# V4-AddOnESP32-V001-komplett.net
KiCad netlist of a schematic drawn in EAGLE
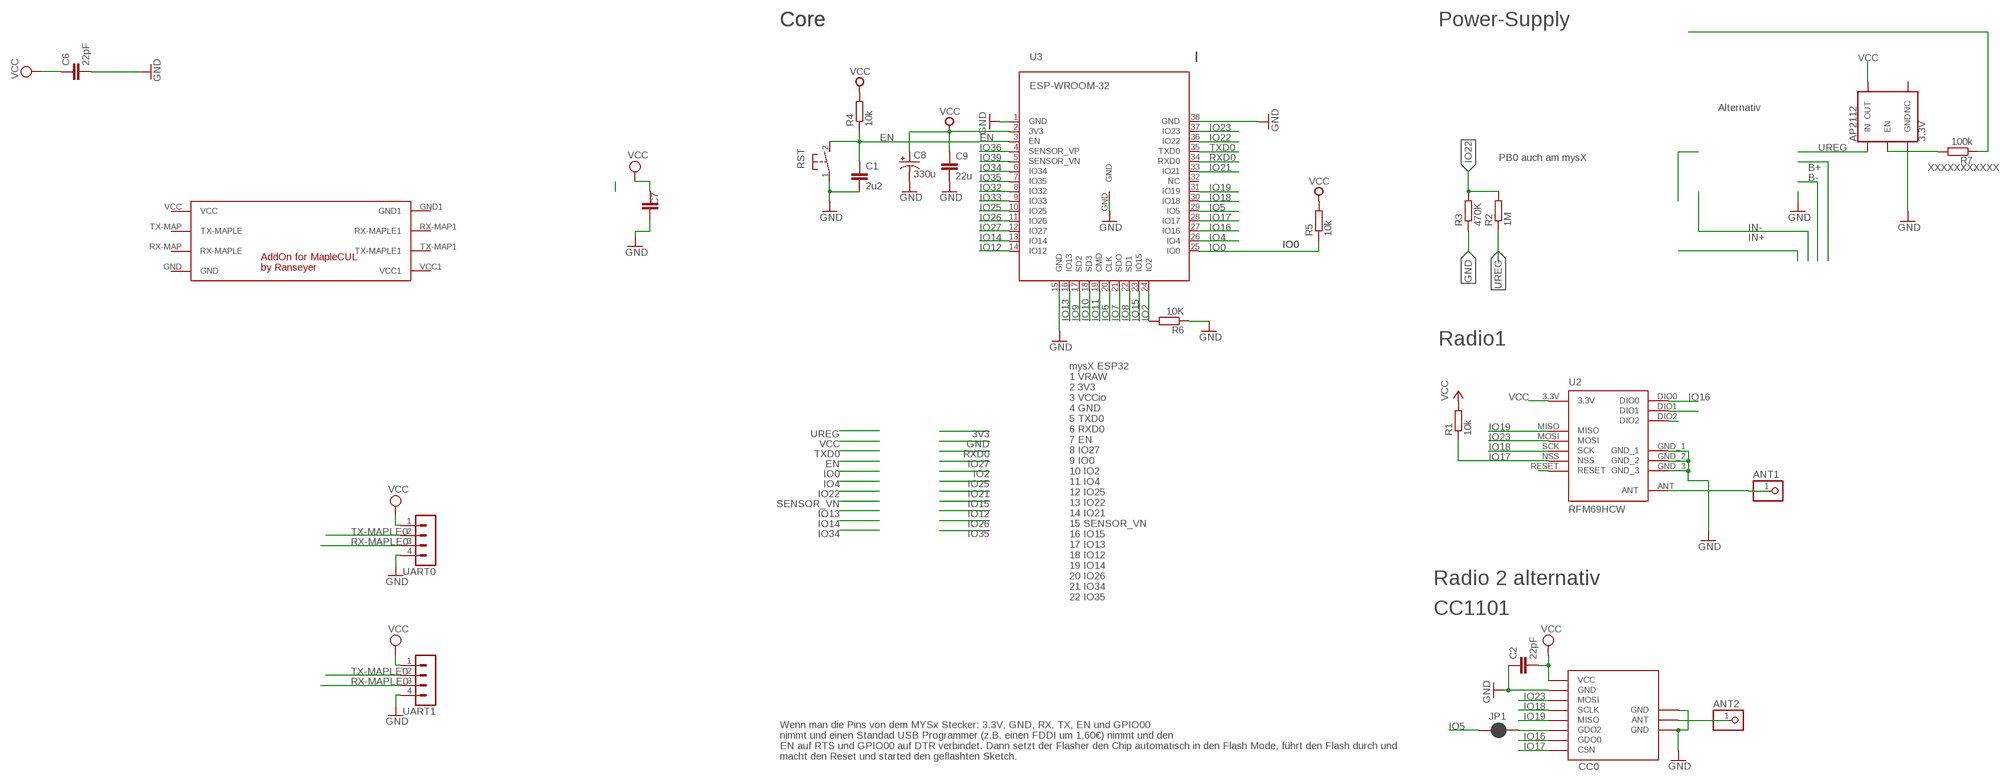
[diagram p0: schematic, sheet 1]

(export (version "E")
  (design (tool "Eeschema 10.0.6"))
  (components
    (comp (ref "ANT1")
      (value "PINHD-1X1")
      (footprint "eagle-import:1X01")
      (libsource (lib "eagle-import") (part "PINHD-1X1"))
    )
    (comp (ref "ANT2")
      (value "PINHD-1X1")
      (footprint "eagle-import:1X01")
      (libsource (lib "eagle-import") (part "PINHD-1X1"))
    )
    (comp (ref "AP2112")
      (value "3.3V")
      (footprint "eagle-import:SOT23-5")
      (libsource (lib "eagle-import") (part "V_REG_AP2112K-3.3V"))
    )
    (comp (ref "C1")
      (value "2u2")
      (footprint "eagle-import:C0805")
      (libsource (lib "eagle-import") (part "rcl@1_C-EUC0805"))
    )
    (comp (ref "C2")
      (value "22pF")
      (footprint "eagle-import:C0805")
      (libsource (lib "eagle-import") (part "C-EUC0805"))
    )
    (comp (ref "C6")
      (value "22pF")
      (footprint "eagle-import:C0805")
      (libsource (lib "eagle-import") (part "rcl_334_C-EUC0805"))
    )
    (comp (ref "C7")
      (value "C-EUC1812")
      (footprint "eagle-import:C1812")
      (libsource (lib "eagle-import") (part "rcl_334_C-EUC1812"))
    )
    (comp (ref "C8")
      (value "330u")
      (footprint "eagle-import:VISHAY_C")
      (libsource (lib "eagle-import") (part "CAP_POLSMD"))
    )
    (comp (ref "C9")
      (value "22u")
      (footprint "eagle-import:C0805")
      (libsource (lib "eagle-import") (part "rcl@1_C-EUC0805"))
    )
    (comp (ref "CC0")
      (value "CC1101")
      (footprint "eagle-import:CC1101_MODULE1_SMD")
      (libsource (lib "eagle-import") (part "CC1101_MODULE1SMD"))
    )
    (comp (ref "JP1")
      (value "JUMPER-SMT_2_NC_PASTE_NO-SILK")
      (footprint "eagle-import:SMT-JUMPER_2_NC_PASTE_NO-SILK")
      (libsource (lib "eagle-import") (part "JUMPER-SMT_2_NC_PASTE_NO-SILK"))
    )
    (comp (ref "R1")
      (value "10k")
      (footprint "eagle-import:M0805")
      (libsource (lib "eagle-import") (part "R-EU_M0805"))
    )
    (comp (ref "R2")
      (value "1M")
      (footprint "eagle-import:M0805")
      (libsource (lib "eagle-import") (part "R-EU_M0805"))
    )
    (comp (ref "R3")
      (value "470K")
      (footprint "eagle-import:M0805")
      (libsource (lib "eagle-import") (part "R-EU_M0805"))
    )
    (comp (ref "R4")
      (value "10k")
      (footprint "eagle-import:M0805")
      (libsource (lib "eagle-import") (part "rcl@1_R-EU_M0805"))
    )
    (comp (ref "R5")
      (value "10k")
      (footprint "eagle-import:R0603")
      (libsource (lib "eagle-import") (part "R-EU_R0603"))
    )
    (comp (ref "R6")
      (value "10K")
      (footprint "eagle-import:M0805")
      (libsource (lib "eagle-import") (part "R-EU_M0805"))
    )
    (comp (ref "R7")
      (value "100k")
      (footprint "eagle-import:M0805")
      (libsource (lib "eagle-import") (part "R-EU_M0805"))
    )
    (comp (ref "RST")
      (value "DTSM-3")
      (footprint "eagle-import:DTSM-3")
      (libsource (lib "eagle-import") (part "DTSM-3"))
    )
    (comp (ref "U$1")
      (value "MAPLE-CUL-ADDON-V01")
      (footprint "eagle-import:MAPLE-CUL-V01")
      (libsource (lib "eagle-import") (part "MAPLE-CUL-ADDON-V01"))
    )
    (comp (ref "U2")
      (value "RFM69HCW")
      (footprint "eagle-import:RFM69HCW-XXXS2")
      (libsource (lib "eagle-import") (part "RFM69HCW"))
    )
    (comp (ref "U3")
      (value "ESP-WROOM-32")
      (footprint "eagle-import:ESP-WROOM-32")
      (libsource (lib "eagle-import") (part "ESP-WROOM-32"))
    )
    (comp (ref "UART0")
      (value "MA04-1")
      (footprint "eagle-import:MA04-1")
      (libsource (lib "eagle-import") (part "MA04-1"))
    )
    (comp (ref "UART1")
      (value "MA04-1")
      (footprint "eagle-import:MA04-1")
      (libsource (lib "eagle-import") (part "MA04-1"))
    )
  )
  (nets
    (net (code "4") (name "/EN") (class "Default")
      (node (ref "C1") (pin "1") (pinfunction "1_1") (pintype "passive"))
      (node (ref "R4") (pin "1") (pinfunction "1_1") (pintype "passive"))
      (node (ref "RST") (pin "2") (pinfunction "2_2") (pintype "passive"))
      (node (ref "U3") (pin "3") (pinfunction "EN_3") (pintype "bidirectional"))
    )
    (net (code "7") (name "/IO0") (class "Default")
      (node (ref "R5") (pin "1") (pinfunction "1_1") (pintype "passive"))
      (node (ref "U3") (pin "25") (pinfunction "IO0_25") (pintype "bidirectional"))
    )
    (net (code "8") (name "/IO2") (class "Default")
      (node (ref "R6") (pin "2") (pinfunction "2_2") (pintype "passive"))
      (node (ref "U3") (pin "24") (pinfunction "IO2_24") (pintype "bidirectional"))
    )
    (net (code "9") (name "/IO4") (class "Default")
      (node (ref "U3") (pin "26") (pinfunction "IO4_26") (pintype "bidirectional"))
    )
    (net (code "10") (name "/IO5") (class "Default")
      (node (ref "JP1") (pin "1") (pinfunction "1_1") (pintype "passive"))
      (node (ref "U3") (pin "29") (pinfunction "IO5_29") (pintype "bidirectional"))
    )
    (net (code "11") (name "/IO6") (class "Default")
      (node (ref "U3") (pin "20") (pinfunction "CLK_20") (pintype "bidirectional"))
    )
    (net (code "12") (name "/IO7") (class "Default")
      (node (ref "U3") (pin "21") (pinfunction "SDO_21") (pintype "bidirectional"))
    )
    (net (code "13") (name "/IO8") (class "Default")
      (node (ref "U3") (pin "22") (pinfunction "SD1_22") (pintype "bidirectional"))
    )
    (net (code "14") (name "/IO9") (class "Default")
      (node (ref "U3") (pin "17") (pinfunction "SD2_17") (pintype "bidirectional"))
    )
    (net (code "15") (name "/IO10") (class "Default")
      (node (ref "U3") (pin "18") (pinfunction "SD3_18") (pintype "bidirectional"))
    )
    (net (code "16") (name "/IO11") (class "Default")
      (node (ref "U3") (pin "19") (pinfunction "CMD_19") (pintype "bidirectional"))
    )
    (net (code "17") (name "/IO12") (class "Default")
      (node (ref "U3") (pin "14") (pinfunction "IO12_14") (pintype "bidirectional"))
    )
    (net (code "18") (name "/IO13") (class "Default")
      (node (ref "U3") (pin "16") (pinfunction "IO13_16") (pintype "bidirectional"))
    )
    (net (code "19") (name "/IO14") (class "Default")
      (node (ref "U3") (pin "13") (pinfunction "IO14_13") (pintype "bidirectional"))
    )
    (net (code "20") (name "/IO15") (class "Default")
      (node (ref "U3") (pin "23") (pinfunction "IO15_23") (pintype "bidirectional"))
    )
    (net (code "21") (name "/IO16") (class "Default")
      (node (ref "CC0") (pin "GDO0") (pinfunction "GDO0_GDO0") (pintype "bidirectional"))
      (node (ref "U2") (pin "DIO0") (pinfunction "DIO0_DIO0") (pintype "bidirectional"))
      (node (ref "U3") (pin "27") (pinfunction "IO16_27") (pintype "bidirectional"))
    )
    (net (code "22") (name "/IO17") (class "Default")
      (node (ref "CC0") (pin "CSN") (pinfunction "CSN_CSN") (pintype "bidirectional"))
      (node (ref "R1") (pin "1") (pinfunction "1_1") (pintype "passive"))
      (node (ref "U2") (pin "NSS") (pinfunction "NSS_NSS") (pintype "input"))
      (node (ref "U3") (pin "28") (pinfunction "IO17_28") (pintype "bidirectional"))
    )
    (net (code "23") (name "/IO18") (class "Default")
      (node (ref "CC0") (pin "SCLK") (pinfunction "SCLK_SCLK") (pintype "bidirectional"))
      (node (ref "U2") (pin "SCK") (pinfunction "SCK_SCK") (pintype "input"))
      (node (ref "U3") (pin "30") (pinfunction "IO18_30") (pintype "bidirectional"))
    )
    (net (code "24") (name "/IO19") (class "Default")
      (node (ref "CC0") (pin "MISO") (pinfunction "MISO_MISO") (pintype "bidirectional"))
      (node (ref "U2") (pin "MISO") (pinfunction "MISO_MISO") (pintype "bidirectional"))
      (node (ref "U3") (pin "31") (pinfunction "IO19_31") (pintype "bidirectional"))
    )
    (net (code "25") (name "/IO21") (class "Default")
      (node (ref "U3") (pin "33") (pinfunction "IO21_33") (pintype "bidirectional"))
    )
    (net (code "26") (name "/IO23") (class "Default")
      (node (ref "CC0") (pin "MOSI") (pinfunction "MOSI_MOSI") (pintype "bidirectional"))
      (node (ref "U2") (pin "MOSI") (pinfunction "MOSI_MOSI") (pintype "input"))
      (node (ref "U3") (pin "37") (pinfunction "IO23_37") (pintype "bidirectional"))
    )
    (net (code "27") (name "/IO25") (class "Default")
      (node (ref "U3") (pin "10") (pinfunction "IO25_10") (pintype "bidirectional"))
    )
    (net (code "28") (name "/IO26") (class "Default")
      (node (ref "U3") (pin "11") (pinfunction "IO26_11") (pintype "bidirectional"))
    )
    (net (code "29") (name "/IO27") (class "Default")
      (node (ref "U3") (pin "12") (pinfunction "IO27_12") (pintype "bidirectional"))
    )
    (net (code "30") (name "/IO32") (class "Default")
      (node (ref "U3") (pin "8") (pinfunction "IO32_8") (pintype "bidirectional"))
    )
    (net (code "31") (name "/IO33") (class "Default")
      (node (ref "U3") (pin "9") (pinfunction "IO33_9") (pintype "bidirectional"))
    )
    (net (code "32") (name "/IO34") (class "Default")
      (node (ref "U3") (pin "6") (pinfunction "IO34_6") (pintype "bidirectional"))
    )
    (net (code "33") (name "/IO35") (class "Default")
      (node (ref "U3") (pin "7") (pinfunction "IO35_7") (pintype "bidirectional"))
    )
    (net (code "34") (name "/IO36") (class "Default")
      (node (ref "U3") (pin "4") (pinfunction "SENSOR_VP_4") (pintype "bidirectional"))
    )
    (net (code "35") (name "/IO39") (class "Default")
      (node (ref "U3") (pin "5") (pinfunction "SENSOR_VN_5") (pintype "bidirectional"))
    )
    (net (code "36") (name "/RX-MAPLE0") (class "Default")
      (node (ref "UART0") (pin "3") (pinfunction "3_3") (pintype "passive"))
      (node (ref "UART1") (pin "3") (pinfunction "3_3") (pintype "passive"))
    )
    (net (code "37") (name "/RXD0") (class "Default")
      (node (ref "U3") (pin "34") (pinfunction "RXD0_34") (pintype "bidirectional"))
    )
    (net (code "39") (name "/TX-MAPLE0") (class "Default")
      (node (ref "UART0") (pin "2") (pinfunction "2_2") (pintype "passive"))
      (node (ref "UART1") (pin "2") (pinfunction "2_2") (pintype "passive"))
    )
    (net (code "40") (name "/TXD0") (class "Default")
      (node (ref "U3") (pin "35") (pinfunction "TXD0_35") (pintype "bidirectional"))
    )
    (net (code "41") (name "GND") (class "Default")
      (node (ref "AP2112") (pin "2") (pinfunction "GND_2") (pintype "input"))
      (node (ref "C1") (pin "2") (pinfunction "2_2") (pintype "passive"))
      (node (ref "C2") (pin "1") (pinfunction "1_1") (pintype "passive"))
      (node (ref "C6") (pin "2") (pinfunction "2_2") (pintype "passive"))
      (node (ref "C7") (pin "1") (pinfunction "1_1") (pintype "passive"))
      (node (ref "C8") (pin "-") (pinfunction "-_-") (pintype "passive"))
      (node (ref "C9") (pin "2") (pinfunction "2_2") (pintype "passive"))
      (node (ref "CC0") (pin "GND@0") (pinfunction "GND_GND@0") (pintype "power_in"))
      (node (ref "CC0") (pin "GND@1") (pinfunction "GND_GND@1") (pintype "power_in"))
      (node (ref "CC0") (pin "GND@2") (pinfunction "GND_GND@2") (pintype "power_in"))
      (node (ref "R3") (pin "1") (pinfunction "1_1") (pintype "passive"))
      (node (ref "R6") (pin "1") (pinfunction "1_1") (pintype "passive"))
      (node (ref "RST") (pin "1") (pinfunction "1_1") (pintype "passive"))
      (node (ref "U2") (pin "GND_1") (pinfunction "GND_1_GND_1") (pintype "power_in"))
      (node (ref "U2") (pin "GND_2") (pinfunction "GND_2_GND_2") (pintype "power_in"))
      (node (ref "U2") (pin "GND_3") (pinfunction "GND_3_GND_3") (pintype "power_in"))
      (node (ref "U3") (pin "1") (pinfunction "GND_1") (pintype "bidirectional"))
      (node (ref "U3") (pin "15") (pinfunction "GND_15") (pintype "bidirectional"))
      (node (ref "U3") (pin "38") (pinfunction "GND_38") (pintype "bidirectional"))
      (node (ref "U3") (pin "GND") (pinfunction "GND_GND") (pintype "bidirectional"))
      (node (ref "UART0") (pin "4") (pinfunction "4_4") (pintype "passive"))
      (node (ref "UART1") (pin "4") (pinfunction "4_4") (pintype "passive"))
    )
    (net (code "42") (name "IO22") (class "Default")
      (node (ref "R2") (pin "2") (pinfunction "2_2") (pintype "passive"))
      (node (ref "R3") (pin "2") (pinfunction "2_2") (pintype "passive"))
      (node (ref "U3") (pin "36") (pinfunction "IO22_36") (pintype "bidirectional"))
    )
    (net (code "43") (name "Net-(ANT1-Pad1)") (class "Default")
      (node (ref "ANT1") (pin "1") (pinfunction "1_1") (pintype "passive"))
      (node (ref "U2") (pin "ANT") (pinfunction "ANT_ANT") (pintype "passive"))
    )
    (net (code "44") (name "Net-(ANT2-Pad1)") (class "Default")
      (node (ref "ANT2") (pin "1") (pinfunction "1_1") (pintype "passive"))
      (node (ref "CC0") (pin "ANT") (pinfunction "ANT_ANT") (pintype "output"))
    )
    (net (code "45") (name "Net-(AP2112-EN)") (class "Default")
      (node (ref "AP2112") (pin "3") (pinfunction "EN_3") (pintype "input"))
      (node (ref "R7") (pin "2") (pinfunction "2_2") (pintype "passive"))
    )
    (net (code "46") (name "Net-(CC0-PadGDO2)") (class "Default")
      (node (ref "CC0") (pin "GDO2") (pinfunction "GDO2_GDO2") (pintype "bidirectional"))
      (node (ref "JP1") (pin "2") (pinfunction "2_2") (pintype "passive"))
    )
    (net (code "47") (name "UREG") (class "Default")
      (node (ref "AP2112") (pin "1") (pinfunction "IN_1") (pintype "input"))
      (node (ref "R2") (pin "1") (pinfunction "1_1") (pintype "passive"))
    )
    (net (code "48") (name "VCC") (class "Default")
      (node (ref "AP2112") (pin "5") (pinfunction "OUT_5") (pintype "passive"))
      (node (ref "C2") (pin "2") (pinfunction "2_2") (pintype "passive"))
      (node (ref "C6") (pin "1") (pinfunction "1_1") (pintype "passive"))
      (node (ref "C7") (pin "2") (pinfunction "2_2") (pintype "passive"))
      (node (ref "C8") (pin "+") (pinfunction "+_+") (pintype "passive"))
      (node (ref "C9") (pin "1") (pinfunction "1_1") (pintype "passive"))
      (node (ref "CC0") (pin "VCC") (pinfunction "VCC_VCC") (pintype "power_in"))
      (node (ref "R1") (pin "2") (pinfunction "2_2") (pintype "passive"))
      (node (ref "R4") (pin "2") (pinfunction "2_2") (pintype "passive"))
      (node (ref "R5") (pin "2") (pinfunction "2_2") (pintype "passive"))
      (node (ref "U2") (pin "3.3V") (pinfunction "3.3V_3.3V") (pintype "power_in"))
      (node (ref "U3") (pin "2") (pinfunction "3V3_2") (pintype "bidirectional"))
      (node (ref "UART0") (pin "1") (pinfunction "1_1") (pintype "passive"))
      (node (ref "UART1") (pin "1") (pinfunction "1_1") (pintype "passive"))
    )
    (net (code "49") (name "unconnected-(AP2112-NC-Pad4)") (class "Default")
      (node (ref "AP2112") (pin "4") (pinfunction "NC_4") (pintype "no_connect"))
    )
    (net (code "50") (name "unconnected-(R7-Pad1)") (class "Default")
      (node (ref "R7") (pin "1") (pinfunction "1_1") (pintype "passive"))
    )
    (net (code "51") (name "unconnected-(U$1-PadGND)") (class "Default")
      (node (ref "U$1") (pin "GND") (pinfunction "GND_GND") (pintype "bidirectional"))
    )
    (net (code "52") (name "unconnected-(U$1-PadGND1)") (class "Default")
      (node (ref "U$1") (pin "GND1") (pinfunction "GND1_GND1") (pintype "bidirectional"))
    )
    (net (code "53") (name "unconnected-(U$1-PadVCC)") (class "Default")
      (node (ref "U$1") (pin "VCC") (pinfunction "VCC_VCC") (pintype "bidirectional"))
    )
    (net (code "54") (name "unconnected-(U$1-PadVCC1)") (class "Default")
      (node (ref "U$1") (pin "VCC1") (pinfunction "VCC1_VCC1") (pintype "bidirectional"))
    )
    (net (code "55") (name "unconnected-(U$1-RX-MAPLE-PadRX-MAP)") (class "Default")
      (node (ref "U$1") (pin "RX-MAP") (pinfunction "RX-MAPLE_RX-MAP") (pintype "bidirectional"))
    )
    (net (code "56") (name "unconnected-(U$1-RX-MAPLE1-PadRX-MAP1)") (class "Default")
      (node (ref "U$1") (pin "RX-MAP1") (pinfunction "RX-MAPLE1_RX-MAP1") (pintype "bidirectional"))
    )
    (net (code "57") (name "unconnected-(U$1-TX-MAPLE-PadTX-MAP)") (class "Default")
      (node (ref "U$1") (pin "TX-MAP") (pinfunction "TX-MAPLE_TX-MAP") (pintype "bidirectional"))
    )
    (net (code "58") (name "unconnected-(U$1-TX-MAPLE1-PadTX-MAP1)") (class "Default")
      (node (ref "U$1") (pin "TX-MAP1") (pinfunction "TX-MAPLE1_TX-MAP1") (pintype "bidirectional"))
    )
    (net (code "59") (name "unconnected-(U2-PadDIO1)") (class "Default")
      (node (ref "U2") (pin "DIO1") (pinfunction "DIO1_DIO1") (pintype "bidirectional"))
    )
    (net (code "60") (name "unconnected-(U2-PadDIO2)") (class "Default")
      (node (ref "U2") (pin "DIO2") (pinfunction "DIO2_DIO2") (pintype "bidirectional"))
    )
    (net (code "61") (name "unconnected-(U2-PadRESET)") (class "Default")
      (node (ref "U2") (pin "RESET") (pinfunction "RESET_RESET") (pintype "input"))
    )
    (net (code "62") (name "unconnected-(U3-NC-Pad32)") (class "Default")
      (node (ref "U3") (pin "32") (pinfunction "NC_32") (pintype "bidirectional"))
    )
  )
)
